# NOVASTACK_Adapter_V0_2.net
KiCad netlist of a schematic drawn in EAGLE
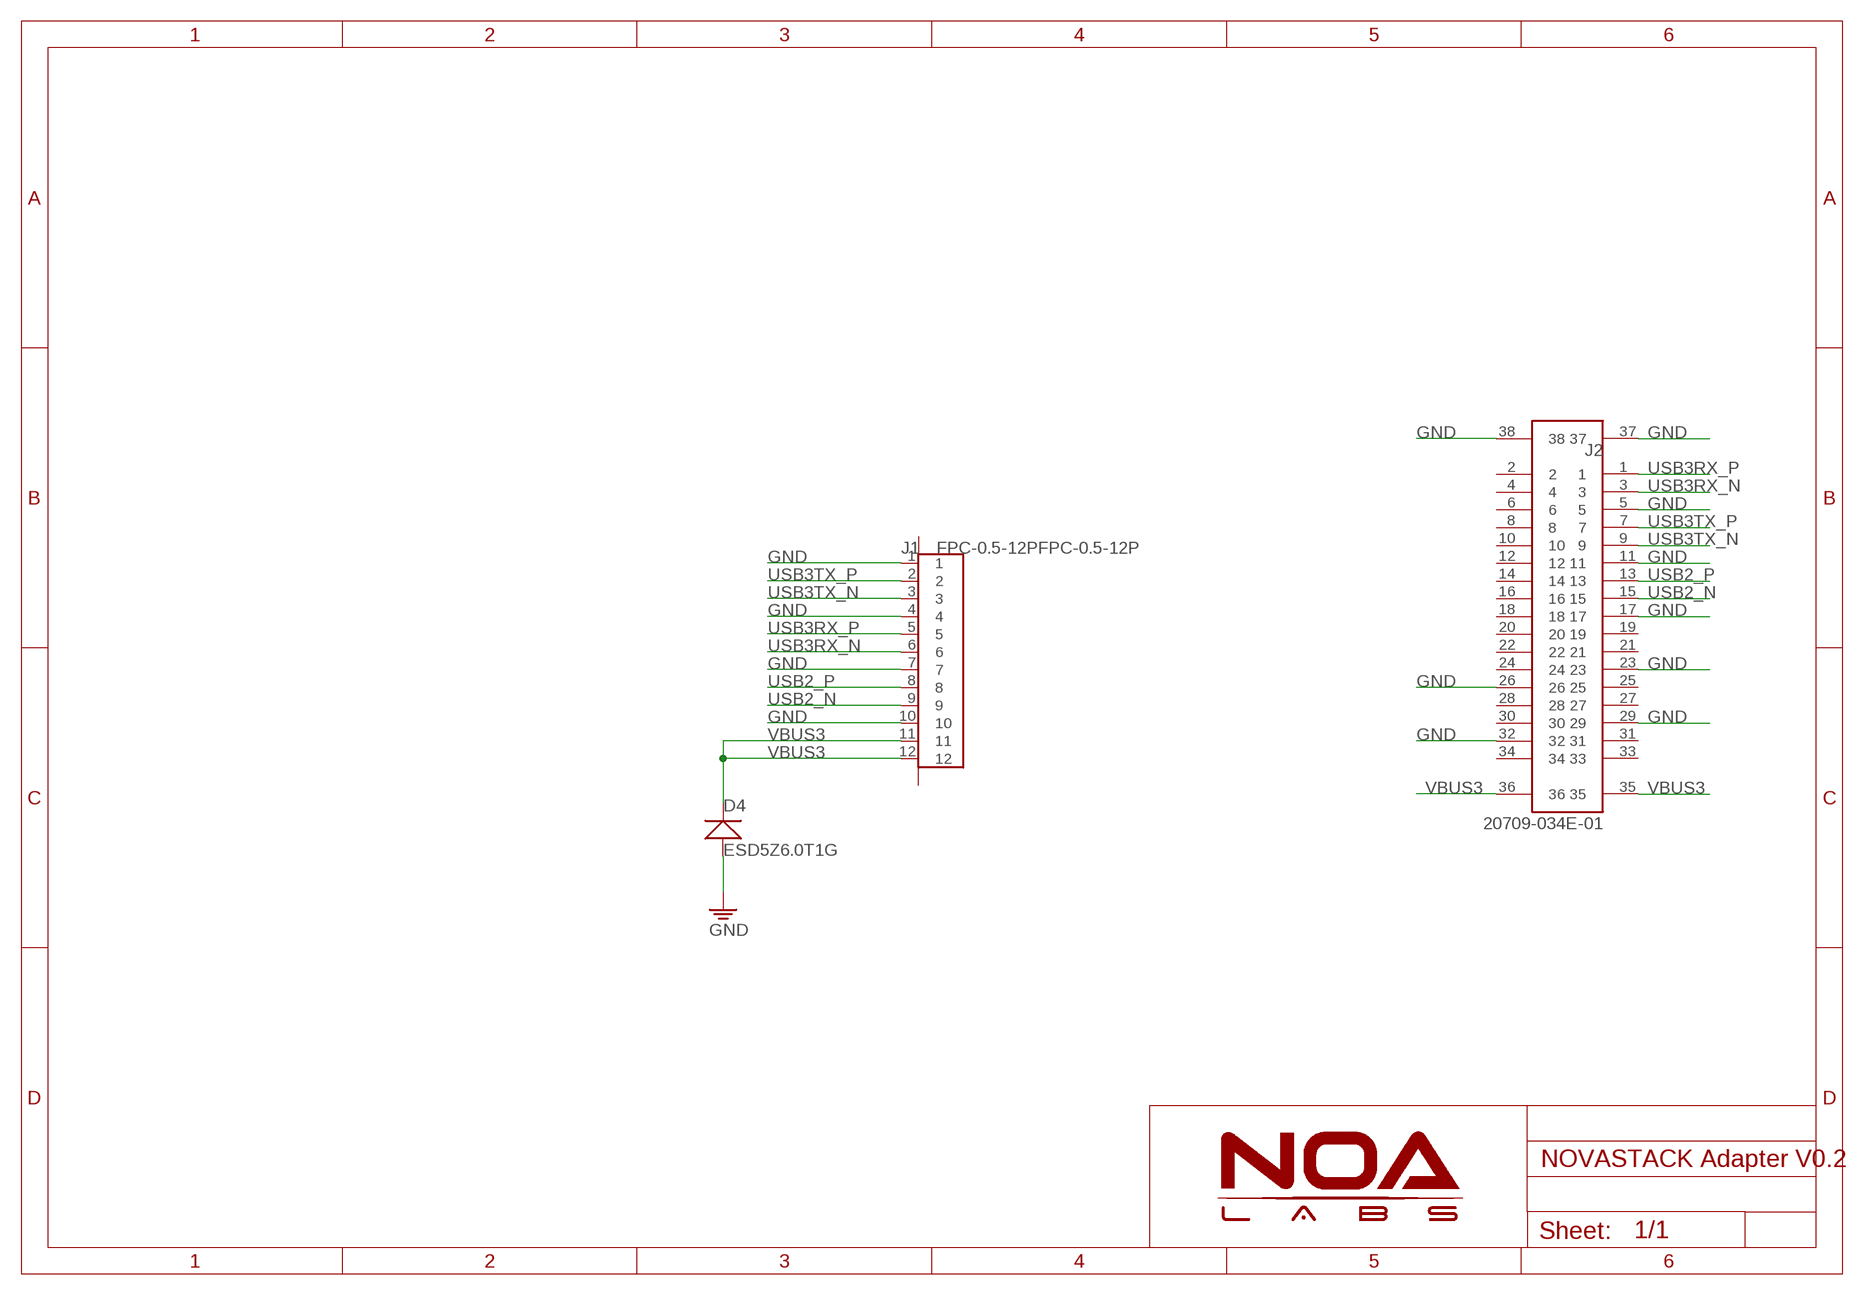
[diagram p0: schematic, sheet 1]

(export (version "E")
  (design (tool "Eeschema 10.0.6"))
  (components
    (comp (ref "D4")
      (value "ESD5Z6.0T1G")
      (footprint "eagle-import:SOD523")
      (libsource (lib "eagle-import") (part "D-0603"))
    )
    (comp (ref "J1")
      (value "FPC-0.5-12PFPC-0.5-12P")
      (footprint "eagle-import:FPC-0.5-12P")
      (libsource (lib "eagle-import") (part "FPC-0.5-12PFPC-0.5-12P"))
    )
    (comp (ref "J2")
      (value "20709-034E-01")
      (footprint "eagle-import:IPEX_20709-034E-01")
      (fields (field (name "MF") "I-PEX"))
      (libsource (lib "eagle-import") (part "20709-034E-01"))
    )
  )
  (nets
    (net (code "1") (name "/USB2_N") (class "Default")
      (node (ref "J1") (pin "9") (pinfunction "9_9") (pintype "bidirectional"))
      (node (ref "J2") (pin "15") (pinfunction "15_15") (pintype "passive"))
    )
    (net (code "2") (name "/USB2_P") (class "Default")
      (node (ref "J1") (pin "8") (pinfunction "8_8") (pintype "bidirectional"))
      (node (ref "J2") (pin "13") (pinfunction "13_13") (pintype "passive"))
    )
    (net (code "3") (name "/USB3RX_N") (class "Default")
      (node (ref "J1") (pin "6") (pinfunction "6_6") (pintype "bidirectional"))
      (node (ref "J2") (pin "3") (pinfunction "3_3") (pintype "passive"))
    )
    (net (code "4") (name "/USB3RX_P") (class "Default")
      (node (ref "J1") (pin "5") (pinfunction "5_5") (pintype "bidirectional"))
      (node (ref "J2") (pin "1") (pinfunction "1_1") (pintype "passive"))
    )
    (net (code "5") (name "/USB3TX_N") (class "Default")
      (node (ref "J1") (pin "3") (pinfunction "3_3") (pintype "bidirectional"))
      (node (ref "J2") (pin "9") (pinfunction "9_9") (pintype "passive"))
    )
    (net (code "6") (name "/USB3TX_P") (class "Default")
      (node (ref "J1") (pin "2") (pinfunction "2_2") (pintype "bidirectional"))
      (node (ref "J2") (pin "7") (pinfunction "7_7") (pintype "passive"))
    )
    (net (code "7") (name "/VBUS3") (class "Default")
      (node (ref "D4") (pin "-") (pinfunction "-_-") (pintype "passive"))
      (node (ref "J1") (pin "11") (pinfunction "11_11") (pintype "bidirectional"))
      (node (ref "J1") (pin "12") (pinfunction "12_12") (pintype "bidirectional"))
      (node (ref "J2") (pin "35") (pinfunction "35_35") (pintype "passive"))
      (node (ref "J2") (pin "36") (pinfunction "36_36") (pintype "passive"))
    )
    (net (code "8") (name "GND") (class "Default")
      (node (ref "D4") (pin "+") (pinfunction "+_+") (pintype "passive"))
      (node (ref "J1") (pin "1") (pinfunction "1_1") (pintype "bidirectional"))
      (node (ref "J1") (pin "10") (pinfunction "10_10") (pintype "bidirectional"))
      (node (ref "J1") (pin "4") (pinfunction "4_4") (pintype "bidirectional"))
      (node (ref "J1") (pin "7") (pinfunction "7_7") (pintype "bidirectional"))
      (node (ref "J2") (pin "11") (pinfunction "11_11") (pintype "passive"))
      (node (ref "J2") (pin "17") (pinfunction "17_17") (pintype "passive"))
      (node (ref "J2") (pin "23") (pinfunction "23_23") (pintype "passive"))
      (node (ref "J2") (pin "26") (pinfunction "26_26") (pintype "passive"))
      (node (ref "J2") (pin "29") (pinfunction "29_29") (pintype "passive"))
      (node (ref "J2") (pin "32") (pinfunction "32_32") (pintype "passive"))
      (node (ref "J2") (pin "37") (pinfunction "37_37") (pintype "passive"))
      (node (ref "J2") (pin "38") (pinfunction "38_38") (pintype "passive"))
      (node (ref "J2") (pin "5") (pinfunction "5_5") (pintype "passive"))
    )
    (net (code "9") (name "unconnected-(J1-G1-PadP$13)") (class "Default")
      (node (ref "J1") (pin "P$13") (pinfunction "G1_P$13") (pintype "bidirectional"))
    )
    (net (code "10") (name "unconnected-(J1-G2-PadP$14)") (class "Default")
      (node (ref "J1") (pin "P$14") (pinfunction "G2_P$14") (pintype "bidirectional"))
    )
    (net (code "11") (name "unconnected-(J2-Pad2)") (class "Default")
      (node (ref "J2") (pin "2") (pinfunction "2_2") (pintype "passive"))
    )
    (net (code "12") (name "unconnected-(J2-Pad4)") (class "Default")
      (node (ref "J2") (pin "4") (pinfunction "4_4") (pintype "passive"))
    )
    (net (code "13") (name "unconnected-(J2-Pad6)") (class "Default")
      (node (ref "J2") (pin "6") (pinfunction "6_6") (pintype "passive"))
    )
    (net (code "14") (name "unconnected-(J2-Pad8)") (class "Default")
      (node (ref "J2") (pin "8") (pinfunction "8_8") (pintype "passive"))
    )
    (net (code "15") (name "unconnected-(J2-Pad10)") (class "Default")
      (node (ref "J2") (pin "10") (pinfunction "10_10") (pintype "passive"))
    )
    (net (code "16") (name "unconnected-(J2-Pad12)") (class "Default")
      (node (ref "J2") (pin "12") (pinfunction "12_12") (pintype "passive"))
    )
    (net (code "17") (name "unconnected-(J2-Pad14)") (class "Default")
      (node (ref "J2") (pin "14") (pinfunction "14_14") (pintype "passive"))
    )
    (net (code "18") (name "unconnected-(J2-Pad16)") (class "Default")
      (node (ref "J2") (pin "16") (pinfunction "16_16") (pintype "passive"))
    )
    (net (code "19") (name "unconnected-(J2-Pad18)") (class "Default")
      (node (ref "J2") (pin "18") (pinfunction "18_18") (pintype "passive"))
    )
    (net (code "20") (name "unconnected-(J2-Pad19)") (class "Default")
      (node (ref "J2") (pin "19") (pinfunction "19_19") (pintype "passive"))
    )
    (net (code "21") (name "unconnected-(J2-Pad20)") (class "Default")
      (node (ref "J2") (pin "20") (pinfunction "20_20") (pintype "passive"))
    )
    (net (code "22") (name "unconnected-(J2-Pad21)") (class "Default")
      (node (ref "J2") (pin "21") (pinfunction "21_21") (pintype "passive"))
    )
    (net (code "23") (name "unconnected-(J2-Pad22)") (class "Default")
      (node (ref "J2") (pin "22") (pinfunction "22_22") (pintype "passive"))
    )
    (net (code "24") (name "unconnected-(J2-Pad24)") (class "Default")
      (node (ref "J2") (pin "24") (pinfunction "24_24") (pintype "passive"))
    )
    (net (code "25") (name "unconnected-(J2-Pad25)") (class "Default")
      (node (ref "J2") (pin "25") (pinfunction "25_25") (pintype "passive"))
    )
    (net (code "26") (name "unconnected-(J2-Pad27)") (class "Default")
      (node (ref "J2") (pin "27") (pinfunction "27_27") (pintype "passive"))
    )
    (net (code "27") (name "unconnected-(J2-Pad28)") (class "Default")
      (node (ref "J2") (pin "28") (pinfunction "28_28") (pintype "passive"))
    )
    (net (code "28") (name "unconnected-(J2-Pad30)") (class "Default")
      (node (ref "J2") (pin "30") (pinfunction "30_30") (pintype "passive"))
    )
    (net (code "29") (name "unconnected-(J2-Pad31)") (class "Default")
      (node (ref "J2") (pin "31") (pinfunction "31_31") (pintype "passive"))
    )
    (net (code "30") (name "unconnected-(J2-Pad33)") (class "Default")
      (node (ref "J2") (pin "33") (pinfunction "33_33") (pintype "passive"))
    )
    (net (code "31") (name "unconnected-(J2-Pad34)") (class "Default")
      (node (ref "J2") (pin "34") (pinfunction "34_34") (pintype "passive"))
    )
  )
)
